# SWD.net
KiCad netlist of a schematic drawn in Altium Designer
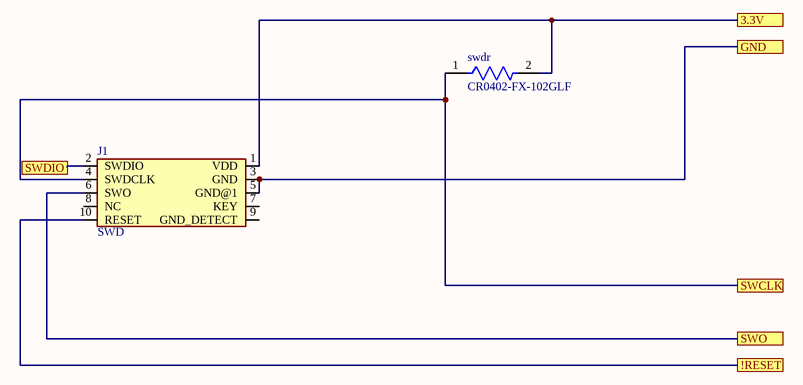
[diagram p0: SWD.SchDoc]

(export (version "E")
  (design (tool "Eeschema 10.0.6"))
  (components
    (comp (ref "J1")
      (value "SWD")
      (footprint "2X10_BOXHEADER")
      (description "SWD WRITEON W/DISP .75X1.4 LAB")
      (fields (field (name "MF") "3M"))
      (libsource (lib "SWD") (part "SWD"))
    )
    (comp (ref "swdr")
      (value "CR0402-FX-102GLF")
      (footprint "FP-CR0402-IPC_C")
      (description "Thick Film Chip Resistors 0402 1kΩ 0.0625W 1% 100ppm/°C")
      (fields (field (name "TOLERANCE") "1%"))
      (libsource (lib "Altium Content Vault") (part "1029c3af85768c4190bb7ad29bc67b5"))
    )
  )
  (nets
    (net (code "1") (name "/!RESET") (class "Default")
      (node (ref "J1") (pin "10") (pinfunction "RESET_10") (pintype "bidirectional"))
    )
    (net (code "2") (name "/3.3V") (class "Default")
      (node (ref "J1") (pin "1") (pinfunction "VDD_1") (pintype "bidirectional"))
      (node (ref "swdr") (pin "2") (pinfunction "2_2") (pintype "passive"))
    )
    (net (code "3") (name "/GND") (class "Default")
      (node (ref "J1") (pin "3") (pinfunction "GND_3") (pintype "bidirectional"))
      (node (ref "J1") (pin "5") (pinfunction "GND@1_5") (pintype "bidirectional"))
    )
    (net (code "4") (name "/SWCLK") (class "Default")
      (node (ref "J1") (pin "4") (pinfunction "SWDCLK_4") (pintype "bidirectional"))
      (node (ref "swdr") (pin "1") (pinfunction "1_1") (pintype "passive"))
    )
    (net (code "5") (name "/SWDIO") (class "Default")
      (node (ref "J1") (pin "2") (pinfunction "SWDIO_2") (pintype "bidirectional"))
    )
    (net (code "6") (name "/SWO") (class "Default")
      (node (ref "J1") (pin "6") (pinfunction "SWO_6") (pintype "bidirectional"))
    )
    (net (code "7") (name "unconnected-(J1-GND_DETECT-Pad9)") (class "Default")
      (node (ref "J1") (pin "9") (pinfunction "GND_DETECT_9") (pintype "bidirectional"))
    )
    (net (code "8") (name "unconnected-(J1-KEY-Pad7)") (class "Default")
      (node (ref "J1") (pin "7") (pinfunction "KEY_7") (pintype "bidirectional"))
    )
    (net (code "9") (name "unconnected-(J1-NC-Pad8)") (class "Default")
      (node (ref "J1") (pin "8") (pinfunction "NC_8") (pintype "bidirectional"))
    )
  )
)
